# v4_1MetroKnome.net
KiCad netlist of a schematic drawn in EAGLE
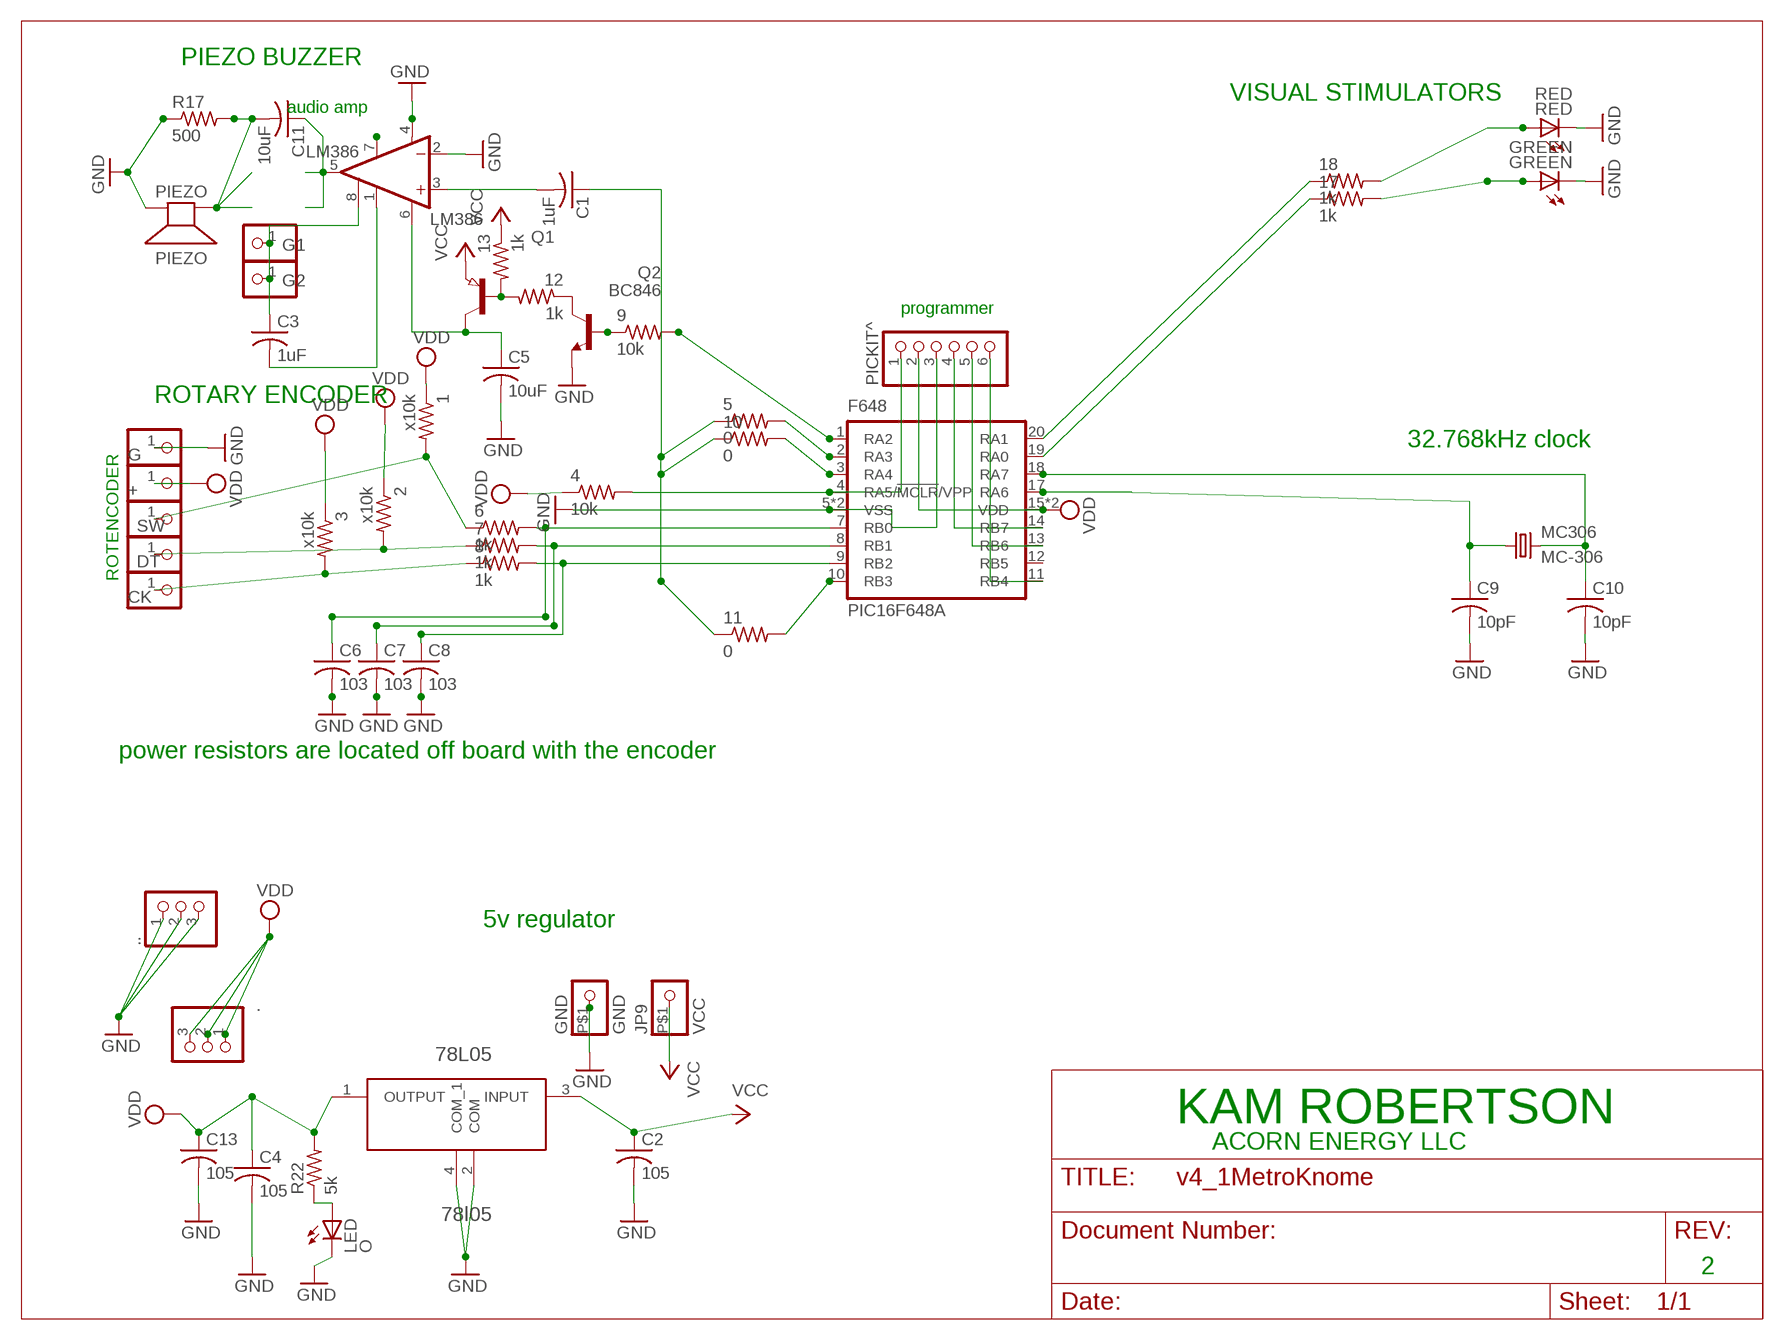
[diagram p0: schematic, sheet 1]

(export (version "E")
  (design (tool "Eeschema 10.0.6"))
  (components
    (comp (ref "+")
      (value "PINHD-1X1CB")
      (footprint "eagle-import:1X01-CLEANBIG")
      (libsource (lib "eagle-import") (part "PINHD-1X1CB"))
    )
    (comp (ref ".")
      (value "PINHD-1X3CB")
      (footprint "eagle-import:1X03-CLEANBIG")
      (libsource (lib "eagle-import") (part "PINHD-1X3CB"))
    )
    (comp (ref "..")
      (value "PINHD-1X3CB")
      (footprint "eagle-import:1X03-CLEANBIG")
      (libsource (lib "eagle-import") (part "PINHD-1X3CB"))
    )
    (comp (ref "1")
      (value "x10k")
      (footprint "eagle-import:R1206")
      (libsource (lib "eagle-import") (part "R-US_R1206"))
    )
    (comp (ref "2")
      (value "x10k")
      (footprint "eagle-import:R1206")
      (libsource (lib "eagle-import") (part "R-US_R1206"))
    )
    (comp (ref "3")
      (value "x10k")
      (footprint "eagle-import:R1206")
      (libsource (lib "eagle-import") (part "R-US_R1206"))
    )
    (comp (ref "4")
      (value "10k")
      (footprint "eagle-import:R1206")
      (libsource (lib "eagle-import") (part "R-US_R1206"))
    )
    (comp (ref "5")
      (value "0")
      (footprint "eagle-import:R1206")
      (libsource (lib "eagle-import") (part "R-US_R1206"))
    )
    (comp (ref "6")
      (value "1k")
      (footprint "eagle-import:R1206")
      (libsource (lib "eagle-import") (part "R-US_R1206"))
    )
    (comp (ref "7")
      (value "1k")
      (footprint "eagle-import:R1206")
      (libsource (lib "eagle-import") (part "R-US_R1206"))
    )
    (comp (ref "8")
      (value "1k")
      (footprint "eagle-import:R1206")
      (libsource (lib "eagle-import") (part "R-US_R1206"))
    )
    (comp (ref "9")
      (value "10k")
      (footprint "eagle-import:R1206")
      (libsource (lib "eagle-import") (part "R-US_R1206"))
    )
    (comp (ref "10")
      (value "0")
      (footprint "eagle-import:R1206")
      (libsource (lib "eagle-import") (part "R-US_R1206"))
    )
    (comp (ref "11")
      (value "0")
      (footprint "eagle-import:R1206")
      (libsource (lib "eagle-import") (part "R-US_R1206"))
    )
    (comp (ref "12")
      (value "1k")
      (footprint "eagle-import:R1206")
      (libsource (lib "eagle-import") (part "R-US_R1206"))
    )
    (comp (ref "13")
      (value "1k")
      (footprint "eagle-import:R1206")
      (libsource (lib "eagle-import") (part "R-US_R1206"))
    )
    (comp (ref "17")
      (value "1k")
      (footprint "eagle-import:R1206")
      (libsource (lib "eagle-import") (part "R-US_R1206"))
    )
    (comp (ref "18")
      (value "1k")
      (footprint "eagle-import:R1206")
      (libsource (lib "eagle-import") (part "R-US_R1206"))
    )
    (comp (ref "78L05")
      (value "78l05")
      (footprint "eagle-import:SOT150P400X160-4N")
      (fields (field (name "MPN") "UA78L05ACPKG3"))
      (libsource (lib "eagle-import") (part "UA78L05ACPKG3"))
    )
    (comp (ref "C1")
      (value "1uF")
      (footprint "eagle-import:C1210")
      (libsource (lib "eagle-import") (part "C-USC1210"))
    )
    (comp (ref "C2")
      (value "105")
      (footprint "eagle-import:C1210")
      (libsource (lib "eagle-import") (part "C-USC1210"))
    )
    (comp (ref "C3")
      (value "1uF")
      (footprint "eagle-import:C1210")
      (libsource (lib "eagle-import") (part "C-USC1210"))
    )
    (comp (ref "C4")
      (value "105")
      (footprint "eagle-import:C1210")
      (libsource (lib "eagle-import") (part "C-USC1210"))
    )
    (comp (ref "C5")
      (value "10uF")
      (footprint "eagle-import:C1210")
      (libsource (lib "eagle-import") (part "C-USC1210"))
    )
    (comp (ref "C6")
      (value "103")
      (footprint "eagle-import:C1210")
      (libsource (lib "eagle-import") (part "C-USC1210"))
    )
    (comp (ref "C7")
      (value "103")
      (footprint "eagle-import:C1210")
      (libsource (lib "eagle-import") (part "C-USC1210"))
    )
    (comp (ref "C8")
      (value "103")
      (footprint "eagle-import:C1210")
      (libsource (lib "eagle-import") (part "C-USC1210"))
    )
    (comp (ref "C9")
      (value "10pF")
      (footprint "eagle-import:C1210")
      (libsource (lib "eagle-import") (part "C-USC1210"))
    )
    (comp (ref "C10")
      (value "10pF")
      (footprint "eagle-import:C1210")
      (libsource (lib "eagle-import") (part "C-USC1210"))
    )
    (comp (ref "C11")
      (value "10uF")
      (footprint "eagle-import:C1210")
      (libsource (lib "eagle-import") (part "C-USC1210"))
    )
    (comp (ref "C13")
      (value "105")
      (footprint "eagle-import:C1210")
      (libsource (lib "eagle-import") (part "C-USC1210"))
    )
    (comp (ref "CK")
      (value "PINHD-1X1CB")
      (footprint "eagle-import:1X01-CLEANBIG")
      (libsource (lib "eagle-import") (part "PINHD-1X1CB"))
    )
    (comp (ref "DT")
      (value "PINHD-1X1CB")
      (footprint "eagle-import:1X01-CLEANBIG")
      (libsource (lib "eagle-import") (part "PINHD-1X1CB"))
    )
    (comp (ref "F648")
      (value "PIC16F648A")
      (footprint "eagle-import:SSOP20")
      (libsource (lib "eagle-import") (part "PIC16F1826/27SS"))
    )
    (comp (ref "G")
      (value "PINHD-1X1CB")
      (footprint "eagle-import:1X01-CLEANBIG")
      (libsource (lib "eagle-import") (part "PINHD-1X1CB"))
    )
    (comp (ref "G1")
      (value "PINHD-1X1CB")
      (footprint "eagle-import:1X01-CLEANBIG")
      (libsource (lib "eagle-import") (part "PINHD-1X1CB"))
    )
    (comp (ref "G2")
      (value "PINHD-1X1CB")
      (footprint "eagle-import:1X01-CLEANBIG")
      (libsource (lib "eagle-import") (part "PINHD-1X1CB"))
    )
    (comp (ref "GND")
      (value "GND")
      (footprint "eagle-import:1X1-BIGPOGO")
      (libsource (lib "eagle-import") (part "PINHD-1X1-BIGPOGO"))
    )
    (comp (ref "GREEN")
      (value "GREEN")
      (footprint "eagle-import:LED5MM")
      (libsource (lib "eagle-import") (part "LED5MM"))
    )
    (comp (ref "JP9")
      (value "VCC")
      (footprint "eagle-import:1X1-BIGPOGO")
      (libsource (lib "eagle-import") (part "PINHD-1X1-BIGPOGO"))
    )
    (comp (ref "LED")
      (value "O")
      (footprint "eagle-import:CHIPLED_1206")
      (libsource (lib "eagle-import") (part "LEDCHIPLED_1206"))
    )
    (comp (ref "LM386")
      (value "LM386")
      (footprint "eagle-import:SO08")
      (libsource (lib "eagle-import") (part "LM386?-M1"))
    )
    (comp (ref "MC306")
      (value "MC-306")
      (footprint "eagle-import:MC-306")
      (fields
        (field (name "MPN") "MC-306 60.0KHZ  100PPM ,12.5PF")
        (field (name "MPN_1") "MC-306 60.0KHZ  100PPM ,12.5PF")
        (field (name "OC_FARNELL") "1278040")
        (field (name "OC_NEWARK") "31M5576")
      )
      (libsource (lib "eagle-import") (part "MC-306"))
    )
    (comp (ref "PICKIT^")
      (value "PINHD-1X6LOCK")
      (footprint "eagle-import:1X06-BIGLOCK")
      (libsource (lib "eagle-import") (part "PINHD-1X6LOCK"))
    )
    (comp (ref "PIEZO")
      (value "PIEZO")
      (footprint "eagle-import:PS12")
      (libsource (lib "eagle-import") (part "SPEAKER/PS12"))
    )
    (comp (ref "Q1")
      (value "PNP-TRANSISTOR_SOT89")
      (footprint "eagle-import:SOT89")
      (libsource (lib "eagle-import") (part "PNP-TRANSISTOR_SOT89"))
    )
    (comp (ref "Q2")
      (value "BC846")
      (footprint "eagle-import:SOT23")
      (libsource (lib "eagle-import") (part "BC846"))
    )
    (comp (ref "R17")
      (value "500")
      (footprint "eagle-import:R1206")
      (libsource (lib "eagle-import") (part "R-US_R1206"))
    )
    (comp (ref "R22")
      (value "5k")
      (footprint "eagle-import:R1206")
      (libsource (lib "eagle-import") (part "R-US_R1206"))
    )
    (comp (ref "RED")
      (value "RED")
      (footprint "eagle-import:LED5MM")
      (libsource (lib "eagle-import") (part "LED5MM"))
    )
    (comp (ref "SW")
      (value "PINHD-1X1CB")
      (footprint "eagle-import:1X01-CLEANBIG")
      (libsource (lib "eagle-import") (part "PINHD-1X1CB"))
    )
  )
  (nets
    (net (code "1") (name "GND") (class "Default")
      (node (ref "..") (pin "1") (pinfunction "1_1") (pintype "passive"))
      (node (ref "..") (pin "2") (pinfunction "2_2") (pintype "passive"))
      (node (ref "..") (pin "3") (pinfunction "3_3") (pintype "passive"))
      (node (ref "78L05") (pin "2") (pinfunction "COM_2") (pintype "power_in"))
      (node (ref "78L05") (pin "4") (pinfunction "COM_1_4") (pintype "power_in"))
      (node (ref "C10") (pin "2") (pinfunction "2_2") (pintype "passive"))
      (node (ref "C13") (pin "2") (pinfunction "2_2") (pintype "passive"))
      (node (ref "C2") (pin "2") (pinfunction "2_2") (pintype "passive"))
      (node (ref "C4") (pin "2") (pinfunction "2_2") (pintype "passive"))
      (node (ref "C5") (pin "2") (pinfunction "2_2") (pintype "passive"))
      (node (ref "C6") (pin "2") (pinfunction "2_2") (pintype "passive"))
      (node (ref "C7") (pin "2") (pinfunction "2_2") (pintype "passive"))
      (node (ref "C8") (pin "2") (pinfunction "2_2") (pintype "passive"))
      (node (ref "C9") (pin "2") (pinfunction "2_2") (pintype "passive"))
      (node (ref "F648") (pin "5") (pinfunction "VSS_5") (pintype "power_in"))
      (node (ref "F648") (pin "6") (pinfunction "VSS_6") (pintype "power_in"))
      (node (ref "G") (pin "1") (pinfunction "1_1") (pintype "passive"))
      (node (ref "GND") (pin "P$1") (pinfunction "1_P$1") (pintype "passive"))
      (node (ref "GREEN") (pin "K") (pinfunction "C_K") (pintype "passive"))
      (node (ref "LED") (pin "C") (pinfunction "C_C") (pintype "passive"))
      (node (ref "LM386") (pin "2") (pinfunction "-IN_2") (pintype "input"))
      (node (ref "LM386") (pin "4") (pinfunction "GND_4") (pintype "power_in"))
      (node (ref "PICKIT^") (pin "3") (pinfunction "3_3") (pintype "passive"))
      (node (ref "PIEZO") (pin "P$2") (pinfunction "-_P$2") (pintype "passive"))
      (node (ref "Q2") (pin "2") (pinfunction "E_2") (pintype "passive"))
      (node (ref "R17") (pin "1") (pinfunction "1_1") (pintype "passive"))
      (node (ref "RED") (pin "K") (pinfunction "C_K") (pintype "passive"))
    )
    (net (code "2") (name "Net-(1-Pad2)") (class "Default")
      (node (ref "1") (pin "2") (pinfunction "2_2") (pintype "passive"))
      (node (ref "6") (pin "1") (pinfunction "1_1") (pintype "passive"))
      (node (ref "SW") (pin "1") (pinfunction "1_1") (pintype "passive"))
    )
    (net (code "3") (name "Net-(2-Pad2)") (class "Default")
      (node (ref "2") (pin "2") (pinfunction "2_2") (pintype "passive"))
      (node (ref "7") (pin "1") (pinfunction "1_1") (pintype "passive"))
      (node (ref "DT") (pin "1") (pinfunction "1_1") (pintype "passive"))
    )
    (net (code "4") (name "Net-(3-Pad2)") (class "Default")
      (node (ref "3") (pin "2") (pinfunction "2_2") (pintype "passive"))
      (node (ref "8") (pin "1") (pinfunction "1_1") (pintype "passive"))
      (node (ref "CK") (pin "1") (pinfunction "1_1") (pintype "passive"))
    )
    (net (code "5") (name "Net-(10-Pad1)") (class "Default")
      (node (ref "10") (pin "1") (pinfunction "1_1") (pintype "passive"))
      (node (ref "11") (pin "1") (pinfunction "1_1") (pintype "passive"))
      (node (ref "5") (pin "1") (pinfunction "1_1") (pintype "passive"))
      (node (ref "C1") (pin "1") (pinfunction "1_1") (pintype "passive"))
    )
    (net (code "6") (name "Net-(17-Pad2)") (class "Default")
      (node (ref "17") (pin "2") (pinfunction "2_2") (pintype "passive"))
      (node (ref "GREEN") (pin "A") (pinfunction "A_A") (pintype "passive"))
    )
    (net (code "7") (name "Net-(18-Pad2)") (class "Default")
      (node (ref "18") (pin "2") (pinfunction "2_2") (pintype "passive"))
      (node (ref "RED") (pin "A") (pinfunction "A_A") (pintype "passive"))
    )
    (net (code "8") (name "Net-(C3-Pad1)") (class "Default")
      (node (ref "C3") (pin "1") (pinfunction "1_1") (pintype "passive"))
      (node (ref "G1") (pin "1") (pinfunction "1_1") (pintype "passive"))
      (node (ref "G2") (pin "1") (pinfunction "1_1") (pintype "passive"))
      (node (ref "LM386") (pin "8") (pinfunction "GAIN_8") (pintype "passive"))
    )
    (net (code "9") (name "Net-(C3-Pad2)") (class "Default")
      (node (ref "C3") (pin "2") (pinfunction "2_2") (pintype "passive"))
      (node (ref "LM386") (pin "1") (pinfunction "GAIN_1") (pintype "passive"))
    )
    (net (code "10") (name "Net-(F648-RA0)") (class "Default")
      (node (ref "17") (pin "1") (pinfunction "1_1") (pintype "passive"))
      (node (ref "F648") (pin "19") (pinfunction "RA0_19") (pintype "bidirectional"))
    )
    (net (code "11") (name "Net-(F648-RA1)") (class "Default")
      (node (ref "18") (pin "1") (pinfunction "1_1") (pintype "passive"))
      (node (ref "F648") (pin "20") (pinfunction "RA1_20") (pintype "bidirectional"))
    )
    (net (code "12") (name "Net-(F648-RA2)") (class "Default")
      (node (ref "9") (pin "2") (pinfunction "2_2") (pintype "passive"))
      (node (ref "F648") (pin "1") (pinfunction "RA2_1") (pintype "bidirectional"))
    )
    (net (code "13") (name "Net-(F648-RA3)") (class "Default")
      (node (ref "5") (pin "2") (pinfunction "2_2") (pintype "passive"))
      (node (ref "F648") (pin "2") (pinfunction "RA3_2") (pintype "bidirectional"))
    )
    (net (code "14") (name "Net-(F648-RA4)") (class "Default")
      (node (ref "10") (pin "2") (pinfunction "2_2") (pintype "passive"))
      (node (ref "F648") (pin "3") (pinfunction "RA4_3") (pintype "bidirectional"))
    )
    (net (code "15") (name "Net-(F648-RA5{slash}~{MCLR}{slash}VPP)") (class "Default")
      (node (ref "4") (pin "2") (pinfunction "2_2") (pintype "passive"))
      (node (ref "F648") (pin "4") (pinfunction "RA5/~{MCLR}/VPP_4") (pintype "bidirectional"))
      (node (ref "PICKIT^") (pin "1") (pinfunction "1_1") (pintype "passive"))
    )
    (net (code "16") (name "Net-(F648-RA6)") (class "Default")
      (node (ref "C9") (pin "1") (pinfunction "1_1") (pintype "passive"))
      (node (ref "F648") (pin "17") (pinfunction "RA6_17") (pintype "bidirectional"))
      (node (ref "MC306") (pin "1") (pinfunction "1_1") (pintype "passive"))
    )
    (net (code "17") (name "Net-(F648-RA7)") (class "Default")
      (node (ref "C10") (pin "1") (pinfunction "1_1") (pintype "passive"))
      (node (ref "F648") (pin "18") (pinfunction "RA7_18") (pintype "bidirectional"))
      (node (ref "MC306") (pin "4") (pinfunction "2_4") (pintype "passive"))
    )
    (net (code "18") (name "Net-(F648-RB0)") (class "Default")
      (node (ref "6") (pin "2") (pinfunction "2_2") (pintype "passive"))
      (node (ref "C6") (pin "1") (pinfunction "1_1") (pintype "passive"))
      (node (ref "F648") (pin "7") (pinfunction "RB0_7") (pintype "bidirectional"))
    )
    (net (code "19") (name "Net-(F648-RB1)") (class "Default")
      (node (ref "7") (pin "2") (pinfunction "2_2") (pintype "passive"))
      (node (ref "C7") (pin "1") (pinfunction "1_1") (pintype "passive"))
      (node (ref "F648") (pin "8") (pinfunction "RB1_8") (pintype "bidirectional"))
    )
    (net (code "20") (name "Net-(F648-RB2)") (class "Default")
      (node (ref "8") (pin "2") (pinfunction "2_2") (pintype "passive"))
      (node (ref "C8") (pin "1") (pinfunction "1_1") (pintype "passive"))
      (node (ref "F648") (pin "9") (pinfunction "RB2_9") (pintype "bidirectional"))
    )
    (net (code "21") (name "Net-(F648-RB3)") (class "Default")
      (node (ref "11") (pin "2") (pinfunction "2_2") (pintype "passive"))
      (node (ref "F648") (pin "10") (pinfunction "RB3_10") (pintype "bidirectional"))
    )
    (net (code "22") (name "Net-(F648-RB4)") (class "Default")
      (node (ref "F648") (pin "11") (pinfunction "RB4_11") (pintype "bidirectional"))
      (node (ref "PICKIT^") (pin "6") (pinfunction "6_6") (pintype "passive"))
    )
    (net (code "23") (name "Net-(F648-RB6)") (class "Default")
      (node (ref "F648") (pin "13") (pinfunction "RB6_13") (pintype "bidirectional"))
      (node (ref "PICKIT^") (pin "5") (pinfunction "5_5") (pintype "passive"))
    )
    (net (code "24") (name "Net-(F648-RB7)") (class "Default")
      (node (ref "F648") (pin "14") (pinfunction "RB7_14") (pintype "bidirectional"))
      (node (ref "PICKIT^") (pin "4") (pinfunction "4_4") (pintype "passive"))
    )
    (net (code "25") (name "Net-(LED-PadA)") (class "Default")
      (node (ref "LED") (pin "A") (pinfunction "A_A") (pintype "passive"))
      (node (ref "R22") (pin "1") (pinfunction "1_1") (pintype "passive"))
    )
    (net (code "26") (name "Net-(LM386-+IN)") (class "Default")
      (node (ref "C1") (pin "2") (pinfunction "2_2") (pintype "passive"))
      (node (ref "LM386") (pin "3") (pinfunction "+IN_3") (pintype "input"))
    )
    (net (code "27") (name "Net-(LM386-OUT)") (class "Default")
      (node (ref "C11") (pin "1") (pinfunction "1_1") (pintype "passive"))
      (node (ref "LM386") (pin "5") (pinfunction "OUT_5") (pintype "output"))
    )
    (net (code "28") (name "Net-(LM386-VS)") (class "Default")
      (node (ref "C5") (pin "1") (pinfunction "1_1") (pintype "passive"))
      (node (ref "LM386") (pin "6") (pinfunction "VS_6") (pintype "power_in"))
      (node (ref "Q1") (pin "2") (pinfunction "C_2") (pintype "passive"))
    )
    (net (code "29") (name "Net-(PIEZO-+)") (class "Default")
      (node (ref "C11") (pin "2") (pinfunction "2_2") (pintype "passive"))
      (node (ref "PIEZO") (pin "P$1") (pinfunction "+_P$1") (pintype "passive"))
      (node (ref "R17") (pin "2") (pinfunction "2_2") (pintype "passive"))
    )
    (net (code "30") (name "Net-(Q1-B)") (class "Default")
      (node (ref "12") (pin "2") (pinfunction "2_2") (pintype "passive"))
      (node (ref "13") (pin "2") (pinfunction "2_2") (pintype "passive"))
      (node (ref "Q1") (pin "1") (pinfunction "B_1") (pintype "passive"))
    )
    (net (code "31") (name "Net-(Q2-B)") (class "Default")
      (node (ref "9") (pin "1") (pinfunction "1_1") (pintype "passive"))
      (node (ref "Q2") (pin "1") (pinfunction "B_1") (pintype "passive"))
    )
    (net (code "32") (name "Net-(Q2-C)") (class "Default")
      (node (ref "12") (pin "1") (pinfunction "1_1") (pintype "passive"))
      (node (ref "Q2") (pin "3") (pinfunction "C_3") (pintype "passive"))
    )
    (net (code "33") (name "VCC") (class "Default")
      (node (ref "13") (pin "1") (pinfunction "1_1") (pintype "passive"))
      (node (ref "78L05") (pin "3") (pinfunction "INPUT_3") (pintype "input"))
      (node (ref "C2") (pin "1") (pinfunction "1_1") (pintype "passive"))
      (node (ref "JP9") (pin "P$1") (pinfunction "1_P$1") (pintype "passive"))
      (node (ref "Q1") (pin "3") (pinfunction "E_3") (pintype "passive"))
    )
    (net (code "34") (name "VDD") (class "Default")
      (node (ref "+") (pin "1") (pinfunction "1_1") (pintype "passive"))
      (node (ref ".") (pin "1") (pinfunction "1_1") (pintype "passive"))
      (node (ref ".") (pin "2") (pinfunction "2_2") (pintype "passive"))
      (node (ref ".") (pin "3") (pinfunction "3_3") (pintype "passive"))
      (node (ref "1") (pin "1") (pinfunction "1_1") (pintype "passive"))
      (node (ref "2") (pin "1") (pinfunction "1_1") (pintype "passive"))
      (node (ref "3") (pin "1") (pinfunction "1_1") (pintype "passive"))
      (node (ref "4") (pin "1") (pinfunction "1_1") (pintype "passive"))
      (node (ref "78L05") (pin "1") (pinfunction "OUTPUT_1") (pintype "output"))
      (node (ref "C13") (pin "1") (pinfunction "1_1") (pintype "passive"))
      (node (ref "C4") (pin "1") (pinfunction "1_1") (pintype "passive"))
      (node (ref "F648") (pin "15") (pinfunction "VDD_15") (pintype "power_in"))
      (node (ref "F648") (pin "16") (pinfunction "VDD_16") (pintype "power_in"))
      (node (ref "PICKIT^") (pin "2") (pinfunction "2_2") (pintype "passive"))
      (node (ref "R22") (pin "2") (pinfunction "2_2") (pintype "passive"))
    )
    (net (code "35") (name "unconnected-(F648-RB5-Pad12)") (class "Default")
      (node (ref "F648") (pin "12") (pinfunction "RB5_12") (pintype "bidirectional"))
    )
    (net (code "36") (name "unconnected-(LM386-BYPASS-Pad7)") (class "Default")
      (node (ref "LM386") (pin "7") (pinfunction "BYPASS_7") (pintype "passive"))
    )
  )
)
